# design.net
KiCad netlist of a schematic drawn in EasyEDA Pro
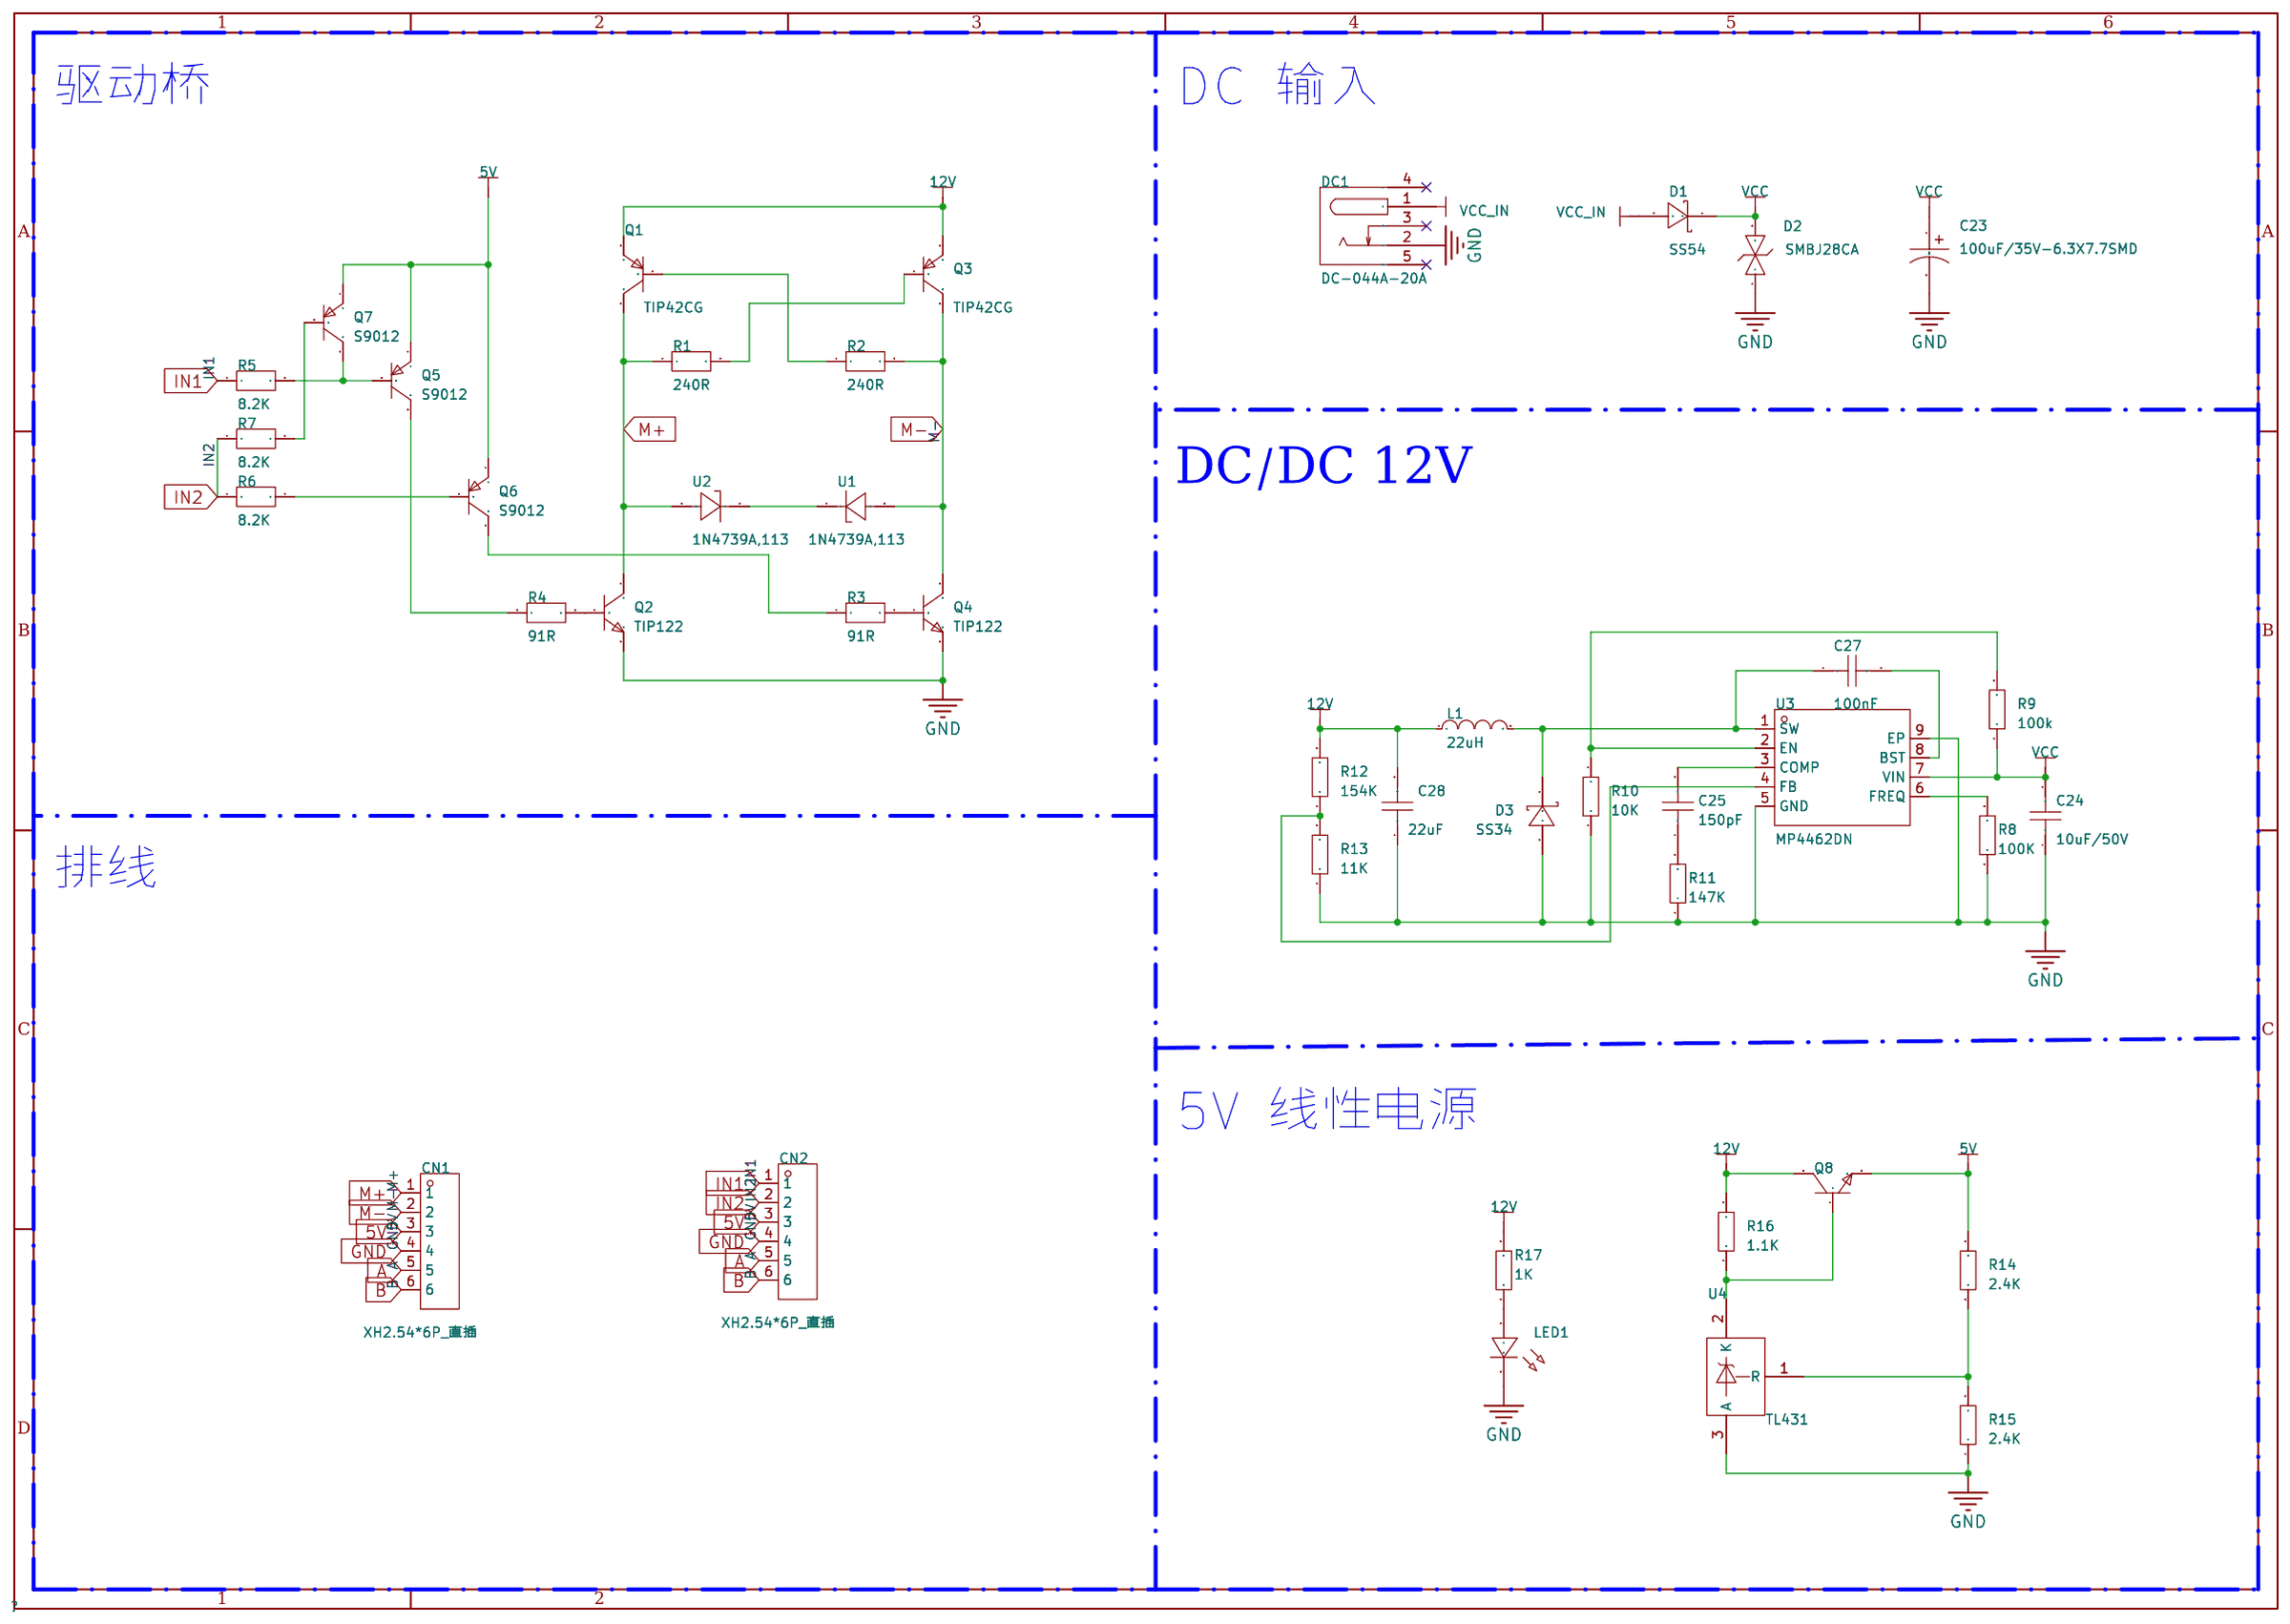
[diagram p0: schematic sheet]

(export (version "E")
  (design (tool "Eeschema 10.0.6"))
  (components
    (comp (ref "C23")
      (value "100uF/35V-6.3X7.7SMD")
      (footprint "easyedapro:CAP-SMD_BD6.3-L6.6-W6.6-FD")
      (libsource (lib "easyedapro") (part "100UF/35V-6.3X7.7SMD"))
    )
    (comp (ref "C24")
      (value "10uF/50V")
      (footprint "easyedapro:C1206")
      (libsource (lib "easyedapro") (part "CapAcitance"))
    )
    (comp (ref "C25")
      (value "150pF")
      (footprint "easyedapro:C1206")
      (libsource (lib "easyedapro") (part "CapAcitance"))
    )
    (comp (ref "C27")
      (value "100nF")
      (footprint "easyedapro:C1206")
      (libsource (lib "easyedapro") (part "CapAcitance"))
    )
    (comp (ref "C28")
      (value "22uF")
      (footprint "easyedapro:C1206")
      (libsource (lib "easyedapro") (part "CapAcitance"))
    )
    (comp (ref "CN1")
      (value "XH2.54*6P_直插")
      (footprint "easyedapro:CONN-TH_XH2.54-6P")
      (libsource (lib "easyedapro") (part "XH2.54*6P_直插"))
    )
    (comp (ref "CN2")
      (value "XH2.54*6P_直插")
      (footprint "easyedapro:CONN-TH_XH2.54-6P")
      (libsource (lib "easyedapro") (part "XH2.54*6P_直插"))
    )
    (comp (ref "D1")
      (value "SS54")
      (footprint "easyedapro:SMA_L4.2-W2.6-LS5.3-RD")
      (fields (field (name "Manufacturer") "CJ(江苏长电/长晶)"))
      (libsource (lib "easyedapro") (part "SS54_C2929944"))
    )
    (comp (ref "D2")
      (value "SMBJ28CA")
      (footprint "easyedapro:SMB_L4.6-W3.6-LS5.3-BI")
      (description "极性:双向;")
      (fields (field (name "Manufacturer") "TWGMC(台湾迪嘉)"))
      (libsource (lib "easyedapro") (part "SMBJ28CA_C726872"))
    )
    (comp (ref "D3")
      (value "SS34")
      (footprint "easyedapro:SMA_L4.3-W2.6-LS5.2-RD")
      (description "二极管配置:独立式;直流反向耐压(Vr):40V;平均整流电流(Io):3A;正向压降(Vf):550mV@3A;反向电流(Ir):500uA@40V;")
      (fields (field (name "Manufacturer") "MDD"))
      (libsource (lib "easyedapro") (part "SS34_C8678"))
    )
    (comp (ref "DC1")
      (value "DC-044A-20A")
      (footprint "easyedapro:DC-IN-TH_DC-044A-20A")
      (description "触点内径:2mm;触点外径:0.9mm;")
      (fields (field (name "Manufacturer") "韩国韩荣"))
      (libsource (lib "easyedapro") (part "DC-044A-20A"))
    )
    (comp (ref "L1")
      (value "22uH")
      (footprint "easyedapro:IND-SMD_L11.0-W10.0")
      (description "额定电流:5A;直流电阻(DCR):64mΩ;精度:±20%;电感值:22uH;")
      (fields
        (field (name "Manufacturer Part") "TMPC1004H-220MG-D")
        (field (name "Manufacturer") "TAI-TECH(台庆)")
      )
      (libsource (lib "easyedapro") (part "TMPC1004H-220MG-D"))
    )
    (comp (ref "LED1")
      (value "~")
      (footprint "easyedapro:LED0805-RD_RED")
      (libsource (lib "easyedapro") (part "LED_G"))
    )
    (comp (ref "Q1")
      (value "TIP42CG")
      (footprint "easyedapro:TO-220-3_L10.0-W4.5-P2.54-L")
      (fields (field (name "Manufacturer") "onsemi(安森美)"))
      (libsource (lib "easyedapro") (part "TIP42CG"))
    )
    (comp (ref "Q2")
      (value "TIP122")
      (footprint "easyedapro:TO-220-3_L10.0-W4.5-P2.54-L")
      (fields (field (name "Manufacturer") "Slkor(萨科微)"))
      (libsource (lib "easyedapro") (part "TIP122_C458982"))
    )
    (comp (ref "Q3")
      (value "TIP42CG")
      (footprint "easyedapro:TO-220-3_L10.0-W4.5-P2.54-L")
      (fields (field (name "Manufacturer") "onsemi(安森美)"))
      (libsource (lib "easyedapro") (part "TIP42CG"))
    )
    (comp (ref "Q4")
      (value "TIP122")
      (footprint "easyedapro:TO-220-3_L10.0-W4.5-P2.54-L")
      (fields (field (name "Manufacturer") "Slkor(萨科微)"))
      (libsource (lib "easyedapro") (part "TIP122_C458982"))
    )
    (comp (ref "Q5")
      (value "S9012")
      (footprint "easyedapro:TO-92-3_L5.1-W4.1-P1.27-L")
      (fields (field (name "Manufacturer") "CJ(江苏长电/长晶)"))
      (libsource (lib "easyedapro") (part "S9012_C12053"))
    )
    (comp (ref "Q6")
      (value "S9012")
      (footprint "easyedapro:TO-92-3_L5.1-W4.1-P1.27-L")
      (fields (field (name "Manufacturer") "CJ(江苏长电/长晶)"))
      (libsource (lib "easyedapro") (part "S9012_C12053"))
    )
    (comp (ref "Q7")
      (value "S9012")
      (footprint "easyedapro:TO-92-3_L5.1-W4.1-P1.27-L")
      (fields (field (name "Manufacturer") "CJ(江苏长电/长晶)"))
      (libsource (lib "easyedapro") (part "S9012_C12053"))
    )
    (comp (ref "Q8")
      (value "~")
      (footprint "easyedapro:S8050_SOT-23")
      (libsource (lib "easyedapro") (part "NPN"))
    )
    (comp (ref "R1")
      (value "240R")
      (footprint "easyedapro:RES-TH_BD2.4-L6.3-P10.30-D0.6")
      (description "电阻类型:金属膜电阻;阻值:2kΩ;精度:±1%;功率:250mW;温度系数:±50ppm/°C;最大工作电压:250V;工作温度范围:-55°C~+125°C;")
      (fields (field (name "Manufacturer Part") "RN1/4W2KFT/BA1") (field (name "Manufacturer") "Tyohm(幸亚电阻)"))
      (libsource (lib "easyedapro") (part "RN 1/4W 2K F T/B A1"))
    )
    (comp (ref "R2")
      (value "240R")
      (footprint "easyedapro:RES-TH_BD2.4-L6.3-P10.30-D0.6")
      (description "电阻类型:金属膜电阻;阻值:2kΩ;精度:±1%;功率:250mW;温度系数:±50ppm/°C;最大工作电压:250V;工作温度范围:-55°C~+125°C;")
      (fields (field (name "Manufacturer Part") "RN1/4W2KFT/BA1") (field (name "Manufacturer") "Tyohm(幸亚电阻)"))
      (libsource (lib "easyedapro") (part "RN 1/4W 2K F T/B A1"))
    )
    (comp (ref "R3")
      (value "91R")
      (footprint "easyedapro:RES-TH_BD2.4-L6.3-P10.30-D0.6")
      (description "电阻类型:金属膜电阻;阻值:2kΩ;精度:±1%;功率:250mW;温度系数:±50ppm/°C;最大工作电压:250V;工作温度范围:-55°C~+125°C;")
      (fields (field (name "Manufacturer Part") "RN1/4W2KFT/BA1") (field (name "Manufacturer") "Tyohm(幸亚电阻)"))
      (libsource (lib "easyedapro") (part "RN 1/4W 2K F T/B A1"))
    )
    (comp (ref "R4")
      (value "91R")
      (footprint "easyedapro:RES-TH_BD2.4-L6.3-P10.30-D0.6")
      (description "电阻类型:金属膜电阻;阻值:2kΩ;精度:±1%;功率:250mW;温度系数:±50ppm/°C;最大工作电压:250V;工作温度范围:-55°C~+125°C;")
      (fields (field (name "Manufacturer Part") "RN1/4W2KFT/BA1") (field (name "Manufacturer") "Tyohm(幸亚电阻)"))
      (libsource (lib "easyedapro") (part "RN 1/4W 2K F T/B A1"))
    )
    (comp (ref "R5")
      (value "8.2K")
      (footprint "easyedapro:RES-TH_BD2.4-L6.3-P10.30-D0.6")
      (description "电阻类型:金属膜电阻;阻值:2kΩ;精度:±1%;功率:250mW;温度系数:±50ppm/°C;最大工作电压:250V;工作温度范围:-55°C~+125°C;")
      (fields (field (name "Manufacturer Part") "RN1/4W2KFT/BA1") (field (name "Manufacturer") "Tyohm(幸亚电阻)"))
      (libsource (lib "easyedapro") (part "RN 1/4W 2K F T/B A1"))
    )
    (comp (ref "R6")
      (value "8.2K")
      (footprint "easyedapro:RES-TH_BD2.4-L6.3-P10.30-D0.6")
      (description "电阻类型:金属膜电阻;阻值:2kΩ;精度:±1%;功率:250mW;温度系数:±50ppm/°C;最大工作电压:250V;工作温度范围:-55°C~+125°C;")
      (fields (field (name "Manufacturer Part") "RN1/4W2KFT/BA1") (field (name "Manufacturer") "Tyohm(幸亚电阻)"))
      (libsource (lib "easyedapro") (part "RN 1/4W 2K F T/B A1"))
    )
    (comp (ref "R7")
      (value "8.2K")
      (footprint "easyedapro:RES-TH_BD2.4-L6.3-P10.30-D0.6")
      (description "电阻类型:金属膜电阻;阻值:2kΩ;精度:±1%;功率:250mW;温度系数:±50ppm/°C;最大工作电压:250V;工作温度范围:-55°C~+125°C;")
      (fields (field (name "Manufacturer Part") "RN1/4W2KFT/BA1") (field (name "Manufacturer") "Tyohm(幸亚电阻)"))
      (libsource (lib "easyedapro") (part "RN 1/4W 2K F T/B A1"))
    )
    (comp (ref "R8") (value "100K") (footprint "easyedapro:R0603") (libsource (lib "easyedapro") (part "电阻")))
    (comp (ref "R9") (value "100k") (footprint "easyedapro:R0603") (libsource (lib "easyedapro") (part "电阻")))
    (comp (ref "R10") (value "10K") (footprint "easyedapro:R0603") (libsource (lib "easyedapro") (part "电阻")))
    (comp (ref "R11")
      (value "147K")
      (footprint "easyedapro:R0603")
      (libsource (lib "easyedapro") (part "电阻"))
    )
    (comp (ref "R12")
      (value "154K")
      (footprint "easyedapro:R0603")
      (libsource (lib "easyedapro") (part "电阻"))
    )
    (comp (ref "R13") (value "11K") (footprint "easyedapro:R0603") (libsource (lib "easyedapro") (part "电阻")))
    (comp (ref "R14")
      (value "2.4K")
      (footprint "easyedapro:R0603")
      (libsource (lib "easyedapro") (part "电阻"))
    )
    (comp (ref "R15")
      (value "2.4K")
      (footprint "easyedapro:R0603")
      (libsource (lib "easyedapro") (part "电阻"))
    )
    (comp (ref "R16")
      (value "1.1K")
      (footprint "easyedapro:R0603")
      (libsource (lib "easyedapro") (part "电阻"))
    )
    (comp (ref "R17") (value "10K") (footprint "easyedapro:R0603") (libsource (lib "easyedapro") (part "电阻")))
    (comp (ref "U1")
      (value "1N4739A,113")
      (footprint "easyedapro:DO-41_BD2.4-L4.7-P8.70-D0.8-RD")
      (fields (field (name "Manufacturer") "Nexperia(安世)"))
      (libsource (lib "easyedapro") (part "1N4739A,113"))
    )
    (comp (ref "U2")
      (value "1N4739A,113")
      (footprint "easyedapro:DO-41_BD2.4-L4.7-P8.70-D0.8-RD")
      (fields (field (name "Manufacturer") "Nexperia(安世)"))
      (libsource (lib "easyedapro") (part "1N4739A,113"))
    )
    (comp (ref "U3")
      (value "MP4462DN")
      (footprint "easyedapro:SOIC-8_L4.9-W3.9-P1.27-LS6.0-BL-EP3.4")
      (libsource (lib "easyedapro") (part "MP4462DN"))
    )
    (comp (ref "U4")
      (value "TL431")
      (footprint "easyedapro:SOT-23-3_L2.9-W1.4-P1.90-LS2.6-BR")
      (fields (field (name "Manufacturer") "JSMSEMI(杰盛微)"))
      (libsource (lib "easyedapro") (part "TL431_C963380"))
    )
  )
  (nets
    (net (code "1") (name "5V") (class "Default")
      (node (ref "CN1") (pin "3") (pinfunction "3_3") (pintype "input"))
      (node (ref "CN2") (pin "3") (pinfunction "3_3") (pintype "input"))
      (node (ref "Q5") (pin "1") (pinfunction "E_1") (pintype "input"))
      (node (ref "Q6") (pin "1") (pinfunction "E_1") (pintype "input"))
      (node (ref "Q7") (pin "1") (pinfunction "E_1") (pintype "input"))
      (node (ref "Q8") (pin "2") (pinfunction "2_2") (pintype "unspecified"))
      (node (ref "R14") (pin "2") (pinfunction "2_2") (pintype "input"))
    )
    (net (code "2") (name "12V") (class "Default")
      (node (ref "C28") (pin "2") (pinfunction "2_2") (pintype "input"))
      (node (ref "L1") (pin "1") (pinfunction "1_1") (pintype "input"))
      (node (ref "Q1") (pin "3") (pinfunction "E_3") (pintype "input"))
      (node (ref "Q3") (pin "3") (pinfunction "E_3") (pintype "input"))
      (node (ref "Q8") (pin "3") (pinfunction "3_3") (pintype "unspecified"))
      (node (ref "R12") (pin "2") (pinfunction "2_2") (pintype "input"))
      (node (ref "R16") (pin "2") (pinfunction "2_2") (pintype "input"))
      (node (ref "R17") (pin "2") (pinfunction "2_2") (pintype "input"))
    )
    (net (code "3") (name "A") (class "Default")
      (node (ref "CN1") (pin "5") (pinfunction "5_5") (pintype "input"))
      (node (ref "CN2") (pin "5") (pinfunction "5_5") (pintype "input"))
    )
    (net (code "4") (name "B") (class "Default")
      (node (ref "CN1") (pin "6") (pinfunction "6_6") (pintype "input"))
      (node (ref "CN2") (pin "6") (pinfunction "6_6") (pintype "input"))
    )
    (net (code "5") (name "GND") (class "Default")
      (node (ref "C23") (pin "2") (pinfunction "2_2") (pintype "input"))
      (node (ref "C24") (pin "1") (pinfunction "1_1") (pintype "input"))
      (node (ref "C28") (pin "1") (pinfunction "1_1") (pintype "input"))
      (node (ref "CN1") (pin "4") (pinfunction "4_4") (pintype "input"))
      (node (ref "CN2") (pin "4") (pinfunction "4_4") (pintype "input"))
      (node (ref "D2") (pin "1") (pinfunction "1_1") (pintype "input"))
      (node (ref "D3") (pin "2") (pinfunction "A_2") (pintype "input"))
      (node (ref "DC1") (pin "2") (pinfunction "2_2") (pintype "input"))
      (node (ref "LED1") (pin "1") (pinfunction "C_1") (pintype "input"))
      (node (ref "Q2") (pin "3") (pinfunction "E_3") (pintype "input"))
      (node (ref "Q4") (pin "3") (pinfunction "E_3") (pintype "input"))
      (node (ref "R10") (pin "1") (pinfunction "1_1") (pintype "input"))
      (node (ref "R11") (pin "1") (pinfunction "1_1") (pintype "input"))
      (node (ref "R13") (pin "1") (pinfunction "1_1") (pintype "input"))
      (node (ref "R15") (pin "1") (pinfunction "1_1") (pintype "input"))
      (node (ref "R8") (pin "1") (pinfunction "1_1") (pintype "input"))
      (node (ref "U3") (pin "5") (pinfunction "GND_5") (pintype "input"))
      (node (ref "U3") (pin "9") (pinfunction "EP_9") (pintype "input"))
      (node (ref "U4") (pin "3") (pinfunction "A_3") (pintype "input"))
    )
    (net (code "6") (name "IN1") (class "Default")
      (node (ref "CN2") (pin "1") (pinfunction "1_1") (pintype "input"))
      (node (ref "R5") (pin "1") (pinfunction "1_1") (pintype "input"))
    )
    (net (code "7") (name "IN2") (class "Default")
      (node (ref "CN2") (pin "2") (pinfunction "2_2") (pintype "input"))
      (node (ref "R6") (pin "1") (pinfunction "1_1") (pintype "input"))
      (node (ref "R7") (pin "1") (pinfunction "1_1") (pintype "input"))
    )
    (net (code "8") (name "M+") (class "Default")
      (node (ref "CN1") (pin "1") (pinfunction "1_1") (pintype "input"))
      (node (ref "Q1") (pin "2") (pinfunction "C_2") (pintype "input"))
      (node (ref "Q2") (pin "2") (pinfunction "C_2") (pintype "input"))
      (node (ref "R1") (pin "1") (pinfunction "1_1") (pintype "input"))
      (node (ref "U2") (pin "2") (pinfunction "A_2") (pintype "input"))
    )
    (net (code "9") (name "M-") (class "Default")
      (node (ref "CN1") (pin "2") (pinfunction "2_2") (pintype "input"))
      (node (ref "Q3") (pin "2") (pinfunction "C_2") (pintype "input"))
      (node (ref "Q4") (pin "2") (pinfunction "C_2") (pintype "input"))
      (node (ref "R2") (pin "2") (pinfunction "2_2") (pintype "input"))
      (node (ref "U1") (pin "2") (pinfunction "A_2") (pintype "input"))
    )
    (net (code "10") (name "Net-(C25-Pad1)") (class "Default")
      (node (ref "C25") (pin "1") (pinfunction "1_1") (pintype "input"))
      (node (ref "R11") (pin "2") (pinfunction "2_2") (pintype "input"))
    )
    (net (code "11") (name "Net-(D3-K)") (class "Default")
      (node (ref "C27") (pin "1") (pinfunction "1_1") (pintype "input"))
      (node (ref "D3") (pin "1") (pinfunction "K_1") (pintype "input"))
      (node (ref "L1") (pin "2") (pinfunction "2_2") (pintype "input"))
      (node (ref "U3") (pin "1") (pinfunction "SW_1") (pintype "input"))
    )
    (net (code "12") (name "Net-(LED1-A)") (class "Default")
      (node (ref "LED1") (pin "2") (pinfunction "A_2") (pintype "input"))
      (node (ref "R17") (pin "1") (pinfunction "1_1") (pintype "input"))
    )
    (net (code "13") (name "Net-(Q1-B)") (class "Default")
      (node (ref "Q1") (pin "1") (pinfunction "B_1") (pintype "input"))
      (node (ref "R2") (pin "1") (pinfunction "1_1") (pintype "input"))
    )
    (net (code "14") (name "Net-(Q2-B)") (class "Default")
      (node (ref "Q2") (pin "1") (pinfunction "B_1") (pintype "input"))
      (node (ref "R4") (pin "2") (pinfunction "2_2") (pintype "input"))
    )
    (net (code "15") (name "Net-(Q3-B)") (class "Default")
      (node (ref "Q3") (pin "1") (pinfunction "B_1") (pintype "input"))
      (node (ref "R1") (pin "2") (pinfunction "2_2") (pintype "input"))
    )
    (net (code "16") (name "Net-(Q4-B)") (class "Default")
      (node (ref "Q4") (pin "1") (pinfunction "B_1") (pintype "input"))
      (node (ref "R3") (pin "2") (pinfunction "2_2") (pintype "input"))
    )
    (net (code "17") (name "Net-(Q5-B)") (class "Default")
      (node (ref "Q5") (pin "2") (pinfunction "B_2") (pintype "input"))
      (node (ref "Q7") (pin "3") (pinfunction "C_3") (pintype "input"))
      (node (ref "R5") (pin "2") (pinfunction "2_2") (pintype "input"))
    )
    (net (code "18") (name "Net-(Q5-C)") (class "Default")
      (node (ref "Q5") (pin "3") (pinfunction "C_3") (pintype "input"))
      (node (ref "R4") (pin "1") (pinfunction "1_1") (pintype "input"))
    )
    (net (code "19") (name "Net-(Q6-B)") (class "Default")
      (node (ref "Q6") (pin "2") (pinfunction "B_2") (pintype "input"))
      (node (ref "R6") (pin "2") (pinfunction "2_2") (pintype "input"))
    )
    (net (code "20") (name "Net-(Q6-C)") (class "Default")
      (node (ref "Q6") (pin "3") (pinfunction "C_3") (pintype "input"))
      (node (ref "R3") (pin "1") (pinfunction "1_1") (pintype "input"))
    )
    (net (code "21") (name "Net-(Q7-B)") (class "Default")
      (node (ref "Q7") (pin "2") (pinfunction "B_2") (pintype "input"))
      (node (ref "R7") (pin "2") (pinfunction "2_2") (pintype "input"))
    )
    (net (code "22") (name "Net-(U1-K)") (class "Default")
      (node (ref "U1") (pin "1") (pinfunction "K_1") (pintype "input"))
      (node (ref "U2") (pin "1") (pinfunction "K_1") (pintype "input"))
    )
    (net (code "23") (name "Net-(U3-BST)") (class "Default")
      (node (ref "C27") (pin "2") (pinfunction "2_2") (pintype "input"))
      (node (ref "U3") (pin "8") (pinfunction "BST_8") (pintype "input"))
    )
    (net (code "24") (name "Net-(U3-COMP)") (class "Default")
      (node (ref "C25") (pin "2") (pinfunction "2_2") (pintype "input"))
      (node (ref "U3") (pin "3") (pinfunction "COMP_3") (pintype "input"))
    )
    (net (code "25") (name "Net-(U3-EN)") (class "Default")
      (node (ref "R10") (pin "2") (pinfunction "2_2") (pintype "input"))
      (node (ref "R9") (pin "2") (pinfunction "2_2") (pintype "input"))
      (node (ref "U3") (pin "2") (pinfunction "EN_2") (pintype "input"))
    )
    (net (code "26") (name "Net-(U3-FB)") (class "Default")
      (node (ref "R12") (pin "1") (pinfunction "1_1") (pintype "input"))
      (node (ref "R13") (pin "2") (pinfunction "2_2") (pintype "input"))
      (node (ref "U3") (pin "4") (pinfunction "FB_4") (pintype "input"))
    )
    (net (code "27") (name "Net-(U3-FREQ)") (class "Default")
      (node (ref "R8") (pin "2") (pinfunction "2_2") (pintype "input"))
      (node (ref "U3") (pin "6") (pinfunction "FREQ_6") (pintype "input"))
    )
    (net (code "28") (name "Net-(U4-K)") (class "Default")
      (node (ref "Q8") (pin "1") (pinfunction "1_1") (pintype "unspecified"))
      (node (ref "R16") (pin "1") (pinfunction "1_1") (pintype "input"))
      (node (ref "U4") (pin "2") (pinfunction "K_2") (pintype "input"))
    )
    (net (code "29") (name "Net-(U4-R)") (class "Default")
      (node (ref "R14") (pin "1") (pinfunction "1_1") (pintype "input"))
      (node (ref "R15") (pin "2") (pinfunction "2_2") (pintype "input"))
      (node (ref "U4") (pin "1") (pinfunction "R_1") (pintype "input"))
    )
    (net (code "30") (name "VCC") (class "Default")
      (node (ref "C23") (pin "1") (pinfunction "1_1") (pintype "input"))
      (node (ref "C24") (pin "2") (pinfunction "2_2") (pintype "input"))
      (node (ref "D1") (pin "1") (pinfunction "C_1") (pintype "input"))
      (node (ref "D2") (pin "2") (pinfunction "2_2") (pintype "input"))
      (node (ref "R9") (pin "1") (pinfunction "1_1") (pintype "input"))
      (node (ref "U3") (pin "7") (pinfunction "VIN_7") (pintype "input"))
    )
    (net (code "31") (name "VCC_IN") (class "Default")
      (node (ref "D1") (pin "2") (pinfunction "A_2") (pintype "input"))
      (node (ref "DC1") (pin "1") (pinfunction "1_1") (pintype "input"))
    )
    (net (code "32") (name "unconnected-(DC1-Pad3)") (class "Default")
      (node (ref "DC1") (pin "3") (pinfunction "3_3") (pintype "input+no_connect"))
    )
    (net (code "33") (name "unconnected-(DC1-Pad4)") (class "Default")
      (node (ref "DC1") (pin "4") (pinfunction "4_4") (pintype "input+no_connect"))
    )
    (net (code "34") (name "unconnected-(DC1-Pad5)") (class "Default")
      (node (ref "DC1") (pin "5") (pinfunction "5_5") (pintype "input+no_connect"))
    )
  )
)
